# Sheet1.net
KiCad netlist of a schematic drawn in Altium Designer
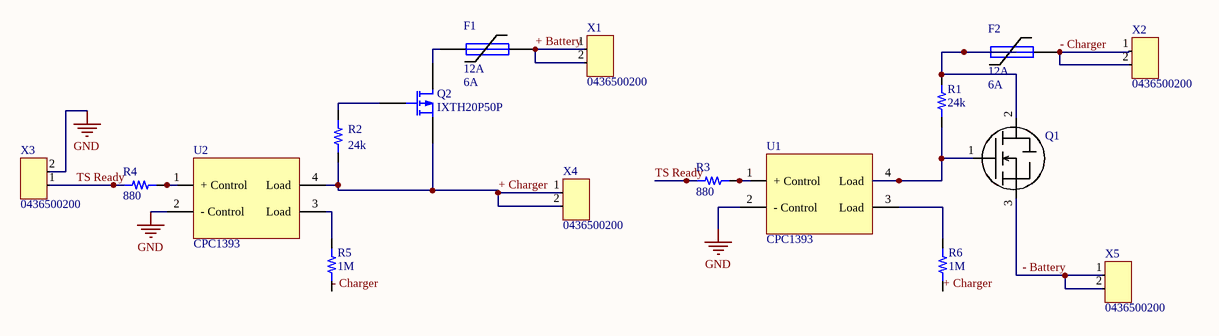
[diagram p0: Sheet1.SchDoc]

(export (version "E")
  (design (tool "Eeschema 10.0.6"))
  (components
    (comp (ref "F1")
      (value "12A")
      (footprint "PIN-W2/E2.8")
      (description "Fuse")
      (fields
        (field (name "I_HOLD") "6A")
        (field (name "MFRPARTNO") "2920L600/12MR")
        (field (name "PUBLISHER") "Altium Limited")
      )
      (libsource (lib "Altium-Lib") (part "PTC Fuse"))
    )
    (comp (ref "F2")
      (value "12A")
      (footprint "PIN-W2/E2.8")
      (description "Fuse")
      (fields
        (field (name "I_HOLD") "6A")
        (field (name "MFRPARTNO") "2920L600/12MR")
        (field (name "PUBLISHER") "Altium Limited")
      )
      (libsource (lib "Altium-Lib") (part "PTC Fuse"))
    )
    (comp (ref "Q1")
      (value "STW20NK50Z")
      (footprint "TO-247")
      (description "N-Channel 500V 17A (Tc) 190W (Tc) Through Hole TO-247-3")
      (fields (field (name "CREATED_BY") "Lynette") (field (name "UPDATED_BY") "Null"))
      (libsource (lib "Altium-Lib") (part "STW20NK50Z"))
    )
    (comp (ref "Q2")
      (value "IXTH20P50P")
      (footprint "TO-247")
      (description "P-Channel 500V 20A (Tc) 460W (Tc) Through Hole TO-247 (IXTH)")
      (fields (field (name "CREATED_BY") "Lynette") (field (name "UPDATED_BY") "Null"))
      (libsource (lib "Altium-Lib") (part "IXTH20P50P"))
    )
    (comp (ref "R1")
      (value "24k")
      (footprint "Axial 25.4mm Pitch")
      (description "2W TH resistor")
      (fields
        (field (name "TOLERANCE") "5%")
        (field (name "POWER") "2W")
        (field (name "CREATED_BY") "Graydon")
      )
      (libsource (lib "Altium-Lib") (part "Resistor"))
    )
    (comp (ref "R2")
      (value "24k")
      (footprint "Axial 25.4mm Pitch")
      (description "2W TH resistor")
      (fields
        (field (name "TOLERANCE") "5%")
        (field (name "POWER") "2W")
        (field (name "CREATED_BY") "Graydon")
      )
      (libsource (lib "Altium-Lib") (part "Resistor"))
    )
    (comp (ref "R3")
      (value "880")
      (footprint "RES 0805/2012")
      (fields
        (field (name "TOLERANCE") "10%")
        (field (name "POWER") "1/10W")
        (field (name "Comment") "Resistor 820 0805 1/10W 10%")
        (field (name "CREATED_BY") "Nick Mah")
      )
      (libsource (lib "Altium-Lib") (part "Resistor"))
    )
    (comp (ref "R4")
      (value "880")
      (footprint "RES 0805/2012")
      (fields
        (field (name "TOLERANCE") "10%")
        (field (name "POWER") "1/10W")
        (field (name "Comment") "Resistor 820 0805 1/10W 10%")
        (field (name "CREATED_BY") "Nick Mah")
      )
      (libsource (lib "Altium-Lib") (part "Resistor"))
    )
    (comp (ref "R5")
      (value "1M")
      (footprint "Axial 25.4mm Pitch")
      (description "2W TH resistor")
      (fields
        (field (name "TOLERANCE") "5%")
        (field (name "POWER") "2W")
        (field (name "CREATED_BY") "Graydon")
      )
      (libsource (lib "Altium-Lib") (part "Resistor"))
    )
    (comp (ref "R6")
      (value "1M")
      (footprint "Axial 25.4mm Pitch")
      (description "2W TH resistor")
      (fields
        (field (name "TOLERANCE") "5%")
        (field (name "POWER") "2W")
        (field (name "CREATED_BY") "Graydon")
      )
      (libsource (lib "Altium-Lib") (part "Resistor"))
    )
    (comp (ref "U1")
      (value "CPC1393")
      (footprint "CPC1393GR")
      (description "Solid State Relay SPST-NO (1 Form A) 4-SMD (0.300\", 7.62mm)")
      (fields
        (field (name "MFRPARTNO") "CPC1393GRTR")
        (field (name "CREATED_BY") "Lynette")
        (field (name "UPDATED_BY") "Null")
      )
      (libsource (lib "Altium-Lib") (part "CPC1393"))
    )
    (comp (ref "U2")
      (value "CPC1393")
      (footprint "CPC1393GR")
      (description "Solid State Relay SPST-NO (1 Form A) 4-SMD (0.300\", 7.62mm)")
      (fields
        (field (name "MFRPARTNO") "CPC1393GRTR")
        (field (name "CREATED_BY") "Lynette")
        (field (name "UPDATED_BY") "Null")
      )
      (libsource (lib "Altium-Lib") (part "CPC1393"))
    )
    (comp (ref "X1")
      (value "0436500200")
      (footprint "CONN 43650-0200 MOLEX 2PIN")
      (fields (field (name "CREATED_BY") "Nick"))
      (libsource (lib "Altium-Lib") (part "CONN 2POS"))
    )
    (comp (ref "X2")
      (value "0436500200")
      (footprint "CONN 43650-0200 MOLEX 2PIN")
      (fields (field (name "CREATED_BY") "Nick"))
      (libsource (lib "Altium-Lib") (part "CONN 2POS"))
    )
    (comp (ref "X3")
      (value "0436500200")
      (footprint "CONN 43650-0200 MOLEX 2PIN")
      (fields (field (name "CREATED_BY") "Nick"))
      (libsource (lib "") (part "CONN 2POS_1"))
    )
    (comp (ref "X4")
      (value "0436500200")
      (footprint "CONN 43650-0200 MOLEX 2PIN")
      (fields (field (name "CREATED_BY") "Nick"))
      (libsource (lib "Altium-Lib") (part "CONN 2POS"))
    )
    (comp (ref "X5")
      (value "0436500200")
      (footprint "CONN 43650-0200 MOLEX 2PIN")
      (fields (field (name "CREATED_BY") "Nick"))
      (libsource (lib "Altium-Lib") (part "CONN 2POS"))
    )
  )
  (nets
    (net (code "1") (name "/+ Battery") (class "Default")
      (node (ref "F1") (pin "2") (pinfunction "2_2") (pintype "passive"))
      (node (ref "X1") (pin "1") (pintype "input"))
      (node (ref "X1") (pin "2") (pintype "input"))
    )
    (net (code "2") (name "/+ Charger") (class "Default")
      (node (ref "Q2") (pin "3") (pinfunction "S_3") (pintype "passive"))
      (node (ref "R2") (pin "1") (pinfunction "1_1") (pintype "passive"))
      (node (ref "R6") (pin "1") (pinfunction "1_1") (pintype "passive"))
      (node (ref "U2") (pin "4") (pinfunction "Load_4") (pintype "passive"))
      (node (ref "X4") (pin "1") (pintype "input"))
      (node (ref "X4") (pin "2") (pintype "input"))
    )
    (net (code "3") (name "/- Battery") (class "Default")
      (node (ref "Q1") (pin "3") (pinfunction "Source_3") (pintype "passive"))
      (node (ref "X5") (pin "1") (pintype "input"))
      (node (ref "X5") (pin "2") (pintype "input"))
    )
    (net (code "4") (name "/- Charger") (class "Default")
      (node (ref "F2") (pin "2") (pinfunction "2_2") (pintype "passive"))
      (node (ref "R5") (pin "1") (pinfunction "1_1") (pintype "passive"))
      (node (ref "X2") (pin "1") (pintype "input"))
      (node (ref "X2") (pin "2") (pintype "input"))
    )
    (net (code "5") (name "/TS Ready") (class "Default")
      (node (ref "R3") (pin "1") (pinfunction "1_1") (pintype "passive"))
      (node (ref "R4") (pin "1") (pinfunction "1_1") (pintype "passive"))
      (node (ref "X3") (pin "1") (pintype "input"))
    )
    (net (code "6") (name "GND") (class "Default")
      (node (ref "U1") (pin "2") (pinfunction "-_Control_2") (pintype "passive"))
      (node (ref "U2") (pin "2") (pinfunction "-_Control_2") (pintype "passive"))
      (node (ref "X3") (pin "2") (pintype "input"))
    )
    (net (code "7") (name "Net-(Q1-D)") (class "Default")
      (node (ref "F2") (pin "1") (pinfunction "1_1") (pintype "passive"))
      (node (ref "Q1") (pin "2") (pinfunction "D_2") (pintype "passive"))
      (node (ref "R1") (pin "2") (pinfunction "2_2") (pintype "passive"))
    )
    (net (code "8") (name "Net-(Q1-Gate)") (class "Default")
      (node (ref "Q1") (pin "1") (pinfunction "Gate_1") (pintype "passive"))
      (node (ref "R1") (pin "1") (pinfunction "1_1") (pintype "passive"))
      (node (ref "U1") (pin "4") (pinfunction "Load_4") (pintype "passive"))
    )
    (net (code "9") (name "Net-(Q2-D)") (class "Default")
      (node (ref "F1") (pin "1") (pinfunction "1_1") (pintype "passive"))
      (node (ref "Q2") (pin "2") (pinfunction "D_2") (pintype "passive"))
    )
    (net (code "10") (name "Net-(Q2-G)") (class "Default")
      (node (ref "Q2") (pin "1") (pinfunction "G_1") (pintype "passive"))
      (node (ref "R2") (pin "2") (pinfunction "2_2") (pintype "passive"))
    )
    (net (code "11") (name "Net-(R5-Pad2)") (class "Default")
      (node (ref "R5") (pin "2") (pinfunction "2_2") (pintype "passive"))
      (node (ref "U2") (pin "3") (pinfunction "Load_3") (pintype "passive"))
    )
    (net (code "12") (name "Net-(R6-Pad2)") (class "Default")
      (node (ref "R6") (pin "2") (pinfunction "2_2") (pintype "passive"))
      (node (ref "U1") (pin "3") (pinfunction "Load_3") (pintype "passive"))
    )
    (net (code "13") (name "Net-(U1-+_Control)") (class "Default")
      (node (ref "R3") (pin "2") (pinfunction "2_2") (pintype "passive"))
      (node (ref "U1") (pin "1") (pinfunction "+_Control_1") (pintype "passive"))
    )
    (net (code "14") (name "Net-(U2-+_Control)") (class "Default")
      (node (ref "R4") (pin "2") (pinfunction "2_2") (pintype "passive"))
      (node (ref "U2") (pin "1") (pinfunction "+_Control_1") (pintype "passive"))
    )
  )
)
